# 1__MCU_Breakout.net
KiCad netlist of a schematic drawn in Altium Designer
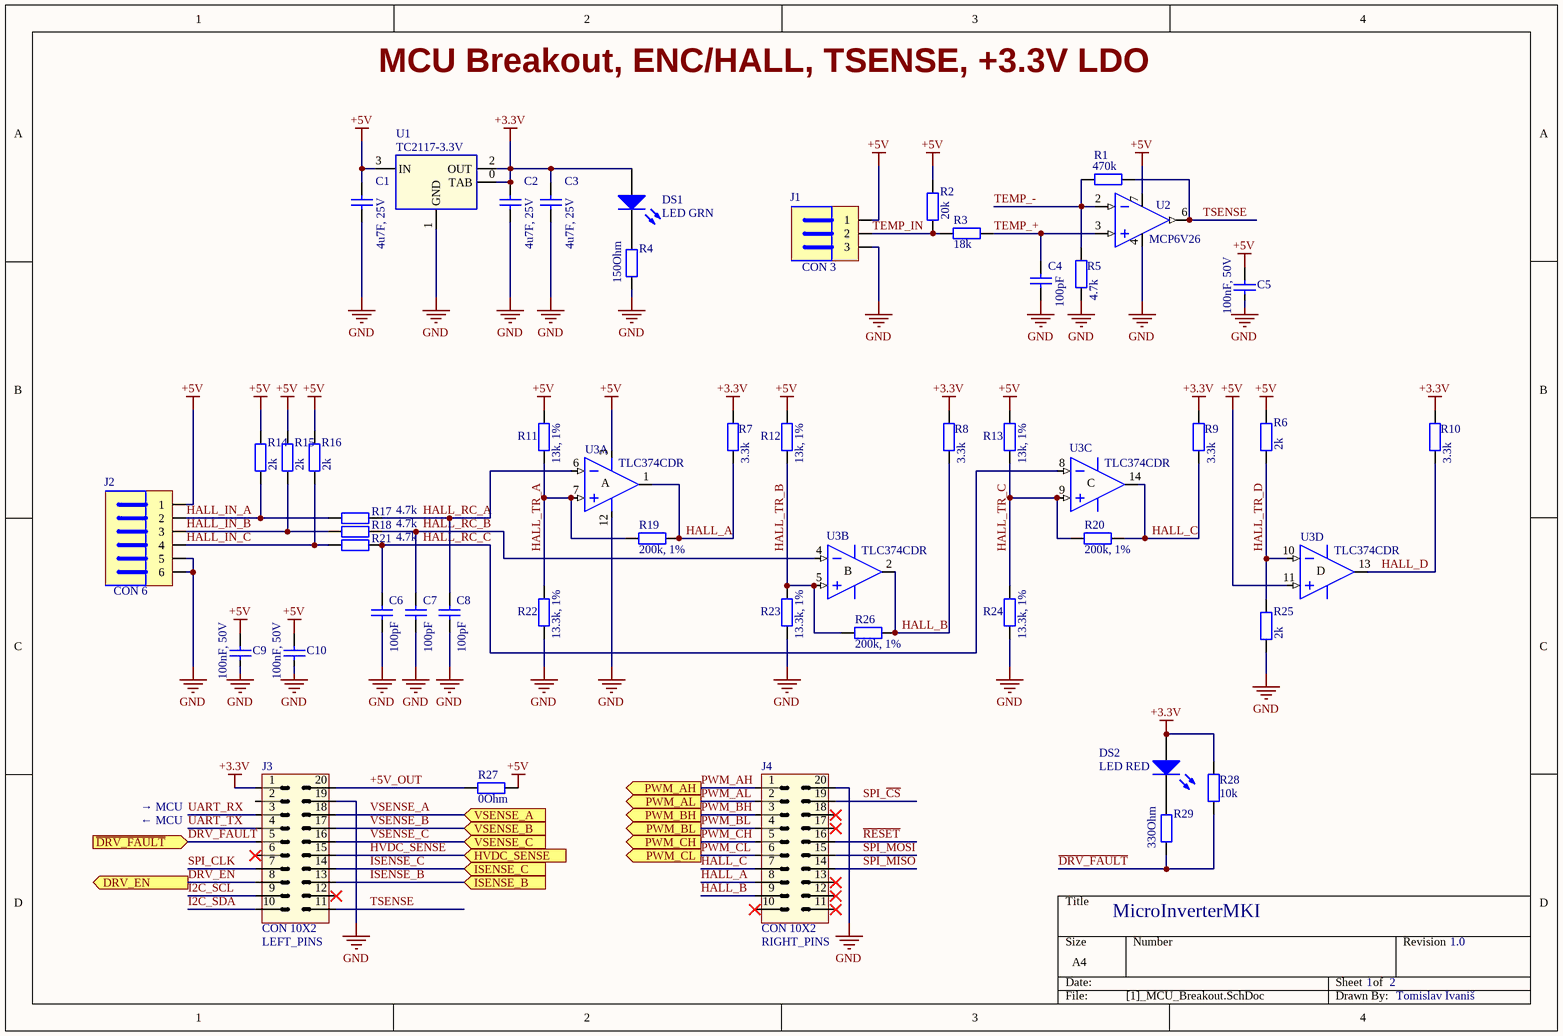
[diagram p0: [1]_MCU_Breakout.SchDoc]

(export (version "E")
  (design (tool "Eeschema 10.0.6"))
  (components
    (comp (ref "C1")
      (value "4u7F, 25V")
      (footprint "0805")
      (description "Capacitor")
      (fields (field (name "MANUFACTURER PART NUMBER") "885012107018"))
      (libsource (lib "MyComponentLib") (part "Cap Semi"))
    )
    (comp (ref "C2")
      (value "4u7F, 25V")
      (footprint "0805")
      (description "Capacitor")
      (fields (field (name "MANUFACTURER PART NUMBER") "885012107018"))
      (libsource (lib "MyComponentLib") (part "Cap Semi"))
    )
    (comp (ref "C3")
      (value "4u7F, 25V")
      (footprint "0805")
      (description "Capacitor")
      (fields (field (name "MANUFACTURER PART NUMBER") "885012107018"))
      (libsource (lib "MyComponentLib") (part "Cap Semi"))
    )
    (comp (ref "C4")
      (value "100pF")
      (footprint "0603")
      (description "885012006036")
      (fields (field (name "MANUFACTURER PART NUMBER") "GCM0335C1E101GA16D"))
      (libsource (lib "MyComponentLib") (part "Cap Semi"))
    )
    (comp (ref "C5")
      (value "100nF, 50V")
      (footprint "0603")
      (description "Capacitor")
      (fields (field (name "MANUFACTURER PART NUMBER") "C0603C104M5RACTU"))
      (libsource (lib "MyComponentLib") (part "Cap Semi"))
    )
    (comp (ref "C6")
      (value "100pF")
      (footprint "0603")
      (description "885012006036")
      (fields (field (name "MANUFACTURER PART NUMBER") "GCM0335C1E101GA16D"))
      (libsource (lib "MyComponentLib") (part "Cap Semi"))
    )
    (comp (ref "C7")
      (value "100pF")
      (footprint "0603")
      (description "885012006036")
      (fields (field (name "MANUFACTURER PART NUMBER") "GCM0335C1E101GA16D"))
      (libsource (lib "MyComponentLib") (part "Cap Semi"))
    )
    (comp (ref "C8")
      (value "100pF")
      (footprint "0603")
      (description "885012006036")
      (fields (field (name "MANUFACTURER PART NUMBER") "GCM0335C1E101GA16D"))
      (libsource (lib "MyComponentLib") (part "Cap Semi"))
    )
    (comp (ref "C9")
      (value "100nF, 50V")
      (footprint "0603")
      (description "Capacitor")
      (fields (field (name "MANUFACTURER PART NUMBER") "C0603C104M5RACTU"))
      (libsource (lib "MyComponentLib") (part "Cap Semi"))
    )
    (comp (ref "C10")
      (value "100nF, 50V")
      (footprint "0603")
      (description "Capacitor")
      (fields (field (name "MANUFACTURER PART NUMBER") "C0603C104M5RACTU"))
      (libsource (lib "MyComponentLib") (part "Cap Semi"))
    )
    (comp (ref "DS1")
      (value "LED GRN")
      (footprint "0805LED")
      (description "Typical RED, GREEN, YELLOW, AMBER GaAs LED")
      (fields (field (name "MANUFACTURER PART NUMBER") "LTST-S220GKT"))
      (libsource (lib "MyComponentLib") (part "LED"))
    )
    (comp (ref "DS2")
      (value "LED RED")
      (footprint "0805LED")
      (description "Typical RED, GREEN, YELLOW, AMBER GaAs LED")
      (fields (field (name "MANUFACTURER PART NUMBER") "LTST-C170KRKT"))
      (libsource (lib "MyComponentLib") (part "LED"))
    )
    (comp (ref "J1")
      (value "CON 3")
      (footprint "CON 3 MOLEX SL")
      (fields (field (name "MANUFACTURER PART NUMBER") "70553-0002"))
      (libsource (lib "MyComponentLib") (part "CON 3 SIL Angle"))
    )
    (comp (ref "J2")
      (value "CON 6")
      (footprint "CON 6 MOLEX SL")
      (fields (field (name "MANUFACTURER PART NUMBER") "70553-0040"))
      (libsource (lib "MyComponentLib") (part "CON 6 SIL Angle"))
    )
    (comp (ref "J3")
      (value "CON 10X2")
      (footprint "CON 20 HEADER - (ALT) - INVERTED")
      (fields (field (name "MANUFACTURER PART NUMBER") "68683-305LF"))
      (libsource (lib "MyComponentLib") (part "CON 10X2"))
    )
    (comp (ref "J4")
      (value "CON 10X2")
      (footprint "CON 20 HEADER - (ALT) - INVERTED")
      (fields (field (name "MANUFACTURER PART NUMBER") "68683-305LF"))
      (libsource (lib "MyComponentLib") (part "CON 10X2"))
    )
    (comp (ref "R1")
      (value "470k")
      (footprint "0805")
      (description "CR0805-JW-680ELF")
      (fields (field (name "MANUFACTURER PART NUMBER") "CR0805-FX-4703ELF"))
      (libsource (lib "") (part "Res_3"))
    )
    (comp (ref "R2")
      (value "20k")
      (footprint "0805")
      (description "CR0805-JW-680ELF")
      (fields (field (name "MANUFACTURER PART NUMBER") "CR0805-FX-2002ELF"))
      (libsource (lib "MyComponentLib") (part "Res"))
    )
    (comp (ref "R3")
      (value "18k")
      (footprint "0805")
      (description "CR0805-JW-680ELF")
      (fields (field (name "MANUFACTURER PART NUMBER") "CR0805-FX-1802ELF"))
      (libsource (lib "") (part "Res_2"))
    )
    (comp (ref "R4")
      (value "150Ohm")
      (footprint "0805")
      (description "CR0805-JW-680ELF")
      (fields (field (name "MANUFACTURER PART NUMBER") "CR0805-JW-151ELF"))
      (libsource (lib "MyComponentLib") (part "Res"))
    )
    (comp (ref "R5")
      (value "4.7k")
      (footprint "0805")
      (description "CR0805-JW-680ELF")
      (fields (field (name "MANUFACTURER PART NUMBER") "CR0805-FX-4701ELF"))
      (libsource (lib "") (part "Res_1"))
    )
    (comp (ref "R6")
      (value "2k")
      (footprint "0805")
      (description "CR0805-JW-680ELF")
      (fields (field (name "MANUFACTURER PART NUMBER") "CR0805-FX-2001ELF"))
      (libsource (lib "MyComponentLib") (part "Res"))
    )
    (comp (ref "R7")
      (value "3.3k")
      (footprint "0805")
      (description "CR0805-JW-680ELF")
      (fields (field (name "MANUFACTURER PART NUMBER") "CR0805-FX-3301ELF"))
      (libsource (lib "MyComponentLib") (part "Res"))
    )
    (comp (ref "R8")
      (value "3.3k")
      (footprint "0805")
      (description "CR0805-JW-680ELF")
      (fields (field (name "MANUFACTURER PART NUMBER") "CR0805-FX-3301ELF"))
      (libsource (lib "MyComponentLib") (part "Res"))
    )
    (comp (ref "R9")
      (value "3.3k")
      (footprint "0805")
      (description "CR0805-JW-680ELF")
      (fields (field (name "MANUFACTURER PART NUMBER") "CR0805-FX-3301ELF"))
      (libsource (lib "MyComponentLib") (part "Res"))
    )
    (comp (ref "R10")
      (value "3.3k")
      (footprint "0805")
      (description "CR0805-JW-680ELF")
      (fields (field (name "MANUFACTURER PART NUMBER") "CR0805-FX-3301ELF"))
      (libsource (lib "MyComponentLib") (part "Res"))
    )
    (comp (ref "R11")
      (value "13k, 1%")
      (footprint "0805")
      (description "CR0805-JW-680ELF")
      (fields (field (name "MANUFACTURER PART NUMBER") "CR0805-FX-1302ELF"))
      (libsource (lib "MyComponentLib") (part "Res"))
    )
    (comp (ref "R12")
      (value "13k, 1%")
      (footprint "0805")
      (description "CR0805-JW-680ELF")
      (fields (field (name "MANUFACTURER PART NUMBER") "CR0805-FX-1302ELF"))
      (libsource (lib "MyComponentLib") (part "Res"))
    )
    (comp (ref "R13")
      (value "13k, 1%")
      (footprint "0805")
      (description "CR0805-JW-680ELF")
      (fields (field (name "MANUFACTURER PART NUMBER") "CR0805-FX-1302ELF"))
      (libsource (lib "MyComponentLib") (part "Res"))
    )
    (comp (ref "R14")
      (value "2k")
      (footprint "0805")
      (description "CR0805-JW-680ELF")
      (fields (field (name "MANUFACTURER PART NUMBER") "CR0805-FX-2001ELF"))
      (libsource (lib "MyComponentLib") (part "Res"))
    )
    (comp (ref "R15")
      (value "2k")
      (footprint "0805")
      (description "CR0805-JW-680ELF")
      (fields (field (name "MANUFACTURER PART NUMBER") "CR0805-FX-2001ELF"))
      (libsource (lib "MyComponentLib") (part "Res"))
    )
    (comp (ref "R16")
      (value "2k")
      (footprint "0805")
      (description "CR0805-JW-680ELF")
      (fields (field (name "MANUFACTURER PART NUMBER") "CR0805-FX-2001ELF"))
      (libsource (lib "MyComponentLib") (part "Res"))
    )
    (comp (ref "R17")
      (value "4.7k")
      (footprint "0805")
      (description "CR0805-JW-680ELF")
      (fields (field (name "MANUFACTURER PART NUMBER") "CR0805-FX-4701ELF"))
      (libsource (lib "") (part "Res_2"))
    )
    (comp (ref "R18")
      (value "4.7k")
      (footprint "0805")
      (description "CR0805-JW-680ELF")
      (fields (field (name "MANUFACTURER PART NUMBER") "CR0805-FX-4701ELF"))
      (libsource (lib "") (part "Res_2"))
    )
    (comp (ref "R19")
      (value "200k, 1%")
      (footprint "0805")
      (description "CR0805-JW-680ELF")
      (fields (field (name "MANUFACTURER PART NUMBER") "CR0805-FX-2003ELF"))
      (libsource (lib "") (part "Res_2"))
    )
    (comp (ref "R20")
      (value "200k, 1%")
      (footprint "0805")
      (description "CR0805-JW-680ELF")
      (fields (field (name "MANUFACTURER PART NUMBER") "CR0805-FX-2003ELF"))
      (libsource (lib "") (part "Res_2"))
    )
    (comp (ref "R21")
      (value "4.7k")
      (footprint "0805")
      (description "CR0805-JW-680ELF")
      (fields (field (name "MANUFACTURER PART NUMBER") "CR0805-FX-4701ELF"))
      (libsource (lib "") (part "Res_2"))
    )
    (comp (ref "R22")
      (value "13.3k, 1%")
      (footprint "0805")
      (description "CR0805-JW-680ELF")
      (fields (field (name "MANUFACTURER PART NUMBER") "CR0805-FX-1332ELF"))
      (libsource (lib "MyComponentLib") (part "Res"))
    )
    (comp (ref "R23")
      (value "13.3k, 1%")
      (footprint "0805")
      (description "CR0805-JW-680ELF")
      (fields (field (name "MANUFACTURER PART NUMBER") "CR0805-FX-1332ELF"))
      (libsource (lib "MyComponentLib") (part "Res"))
    )
    (comp (ref "R24")
      (value "13.3k, 1%")
      (footprint "0805")
      (description "CR0805-JW-680ELF")
      (fields (field (name "MANUFACTURER PART NUMBER") "CR0805-FX-1332ELF"))
      (libsource (lib "MyComponentLib") (part "Res"))
    )
    (comp (ref "R25")
      (value "2k")
      (footprint "0805")
      (description "CR0805-JW-680ELF")
      (fields (field (name "MANUFACTURER PART NUMBER") "CR0805-FX-2001ELF"))
      (libsource (lib "MyComponentLib") (part "Res"))
    )
    (comp (ref "R26")
      (value "200k, 1%")
      (footprint "0805")
      (description "CR0805-JW-680ELF")
      (fields (field (name "MANUFACTURER PART NUMBER") "CR0805-FX-2003ELF"))
      (libsource (lib "") (part "Res_2"))
    )
    (comp (ref "R27")
      (value "0Ohm")
      (footprint "0805")
      (description "Resistor")
      (fields (field (name "MANUFACTURER PART NUMBER") "CR0805-J/-000ELF"))
      (libsource (lib "") (part "Res_2"))
    )
    (comp (ref "R28")
      (value "10k")
      (footprint "0805")
      (description "CR0805-JW-680ELF")
      (fields (field (name "MANUFACTURER PART NUMBER") "CR0805-FX-1002ELF"))
      (libsource (lib "") (part "Res_1"))
    )
    (comp (ref "R29")
      (value "330Ohm")
      (footprint "0805")
      (description "CR0805-JW-680ELF")
      (fields (field (name "MANUFACTURER PART NUMBER") "CR0805-FX-3300ELF"))
      (libsource (lib "MyComponentLib") (part "Res"))
    )
    (comp (ref "U1")
      (value "TC2117-3.3V")
      (footprint "SOT223 (ZLDO)")
      (description "Linear regulator")
      (fields (field (name "MANUFACTURER PART NUMBER") "TC2117-3.3VDBTR"))
      (libsource (lib "MyComponentLib") (part "1117"))
    )
    (comp (ref "U2")
      (value "MCP6V26")
      (footprint "SOIC 8-pin")
      (fields (field (name "MANUFACTURER PART NUMBER") "MCP6V26-E/MS"))
      (libsource (lib "MyComponentLib") (part "OP_AMP_SINGLE_SOIC"))
    )
    (comp (ref "U3")
      (value "TLC374CDR")
      (footprint "SOIC14")
      (description "Comparator, quad, open drain")
      (libsource (lib "MyComponentLib") (part "Comparator Quad"))
    )
  )
  (nets
    (net (code "1") (name "+3.3V") (class "Default")
      (node (ref "C2") (pin "1") (pinfunction "1_1") (pintype "passive"))
      (node (ref "C3") (pin "1") (pinfunction "1_1") (pintype "passive"))
      (node (ref "DS1") (pin "2") (pinfunction "A_2") (pintype "passive"))
      (node (ref "DS2") (pin "2") (pinfunction "A_2") (pintype "passive"))
      (node (ref "J3") (pin "1") (pintype "passive"))
      (node (ref "R10") (pin "1") (pinfunction "1_1") (pintype "passive"))
      (node (ref "R28") (pin "2") (pinfunction "2_2") (pintype "passive"))
      (node (ref "R7") (pin "1") (pinfunction "1_1") (pintype "passive"))
      (node (ref "R8") (pin "1") (pinfunction "1_1") (pintype "passive"))
      (node (ref "R9") (pin "1") (pinfunction "1_1") (pintype "passive"))
      (node (ref "U1") (pin "0") (pinfunction "TAB_0") (pintype "passive"))
      (node (ref "U1") (pin "2") (pinfunction "OUT_2") (pintype "passive"))
    )
    (net (code "2") (name "+5V") (class "Default")
      (node (ref "C1") (pin "1") (pinfunction "1_1") (pintype "passive"))
      (node (ref "C10") (pin "1") (pinfunction "1_1") (pintype "passive"))
      (node (ref "C5") (pin "1") (pinfunction "1_1") (pintype "passive"))
      (node (ref "C9") (pin "1") (pinfunction "1_1") (pintype "passive"))
      (node (ref "J1") (pin "1") (pinfunction "1_1") (pintype "passive"))
      (node (ref "J2") (pin "1") (pinfunction "1_1") (pintype "passive"))
      (node (ref "R11") (pin "1") (pinfunction "1_1") (pintype "passive"))
      (node (ref "R12") (pin "1") (pinfunction "1_1") (pintype "passive"))
      (node (ref "R13") (pin "1") (pinfunction "1_1") (pintype "passive"))
      (node (ref "R14") (pin "1") (pinfunction "1_1") (pintype "passive"))
      (node (ref "R15") (pin "1") (pinfunction "1_1") (pintype "passive"))
      (node (ref "R16") (pin "1") (pinfunction "1_1") (pintype "passive"))
      (node (ref "R2") (pin "1") (pinfunction "1_1") (pintype "passive"))
      (node (ref "R27") (pin "2") (pinfunction "2_2") (pintype "passive"))
      (node (ref "R6") (pin "1") (pinfunction "1_1") (pintype "passive"))
      (node (ref "U1") (pin "3") (pinfunction "IN_3") (pintype "passive"))
      (node (ref "U2") (pin "7") (pinfunction "*_7") (pintype "passive"))
      (node (ref "U3") (pin "11") (pinfunction "IN+_11") (pintype "input"))
      (node (ref "U3") (pin "3") (pinfunction "VDD_3") (pintype "passive"))
    )
    (net (code "3") (name "/+5V_OUT") (class "Default")
      (node (ref "J3") (pin "20") (pintype "passive"))
      (node (ref "R27") (pin "1") (pinfunction "1_1") (pintype "passive"))
    )
    (net (code "4") (name "/DRV_EN") (class "Default") (node (ref "J3") (pin "8") (pintype "passive")))
    (net (code "5") (name "/HALL_A") (class "Default")
      (node (ref "J4") (pin "8") (pintype "passive"))
      (node (ref "R19") (pin "2") (pinfunction "2_2") (pintype "passive"))
      (node (ref "R7") (pin "2") (pinfunction "2_2") (pintype "passive"))
      (node (ref "U3") (pin "1") (pinfunction "OUT_1") (pintype "open_collector"))
    )
    (net (code "6") (name "/HALL_B") (class "Default")
      (node (ref "J4") (pin "9") (pintype "passive"))
      (node (ref "R26") (pin "2") (pinfunction "2_2") (pintype "passive"))
      (node (ref "R8") (pin "2") (pinfunction "2_2") (pintype "passive"))
      (node (ref "U3") (pin "2") (pinfunction "OUT_2") (pintype "open_collector"))
    )
    (net (code "7") (name "/HALL_C") (class "Default")
      (node (ref "J4") (pin "7") (pintype "passive"))
      (node (ref "R20") (pin "2") (pinfunction "2_2") (pintype "passive"))
      (node (ref "R9") (pin "2") (pinfunction "2_2") (pintype "passive"))
      (node (ref "U3") (pin "14") (pinfunction "OUT_14") (pintype "open_collector"))
    )
    (net (code "8") (name "/HALL_D") (class "Default")
      (node (ref "R10") (pin "2") (pinfunction "2_2") (pintype "passive"))
      (node (ref "U3") (pin "13") (pinfunction "OUT_13") (pintype "open_collector"))
    )
    (net (code "9") (name "/HALL_IN_A") (class "Default")
      (node (ref "J2") (pin "2") (pinfunction "2_2") (pintype "passive"))
      (node (ref "R14") (pin "2") (pinfunction "2_2") (pintype "passive"))
      (node (ref "R17") (pin "1") (pinfunction "1_1") (pintype "passive"))
    )
    (net (code "10") (name "/HALL_IN_B") (class "Default")
      (node (ref "J2") (pin "3") (pinfunction "3_3") (pintype "passive"))
      (node (ref "R15") (pin "2") (pinfunction "2_2") (pintype "passive"))
      (node (ref "R18") (pin "1") (pinfunction "1_1") (pintype "passive"))
    )
    (net (code "11") (name "/HALL_IN_C") (class "Default")
      (node (ref "J2") (pin "4") (pinfunction "4_4") (pintype "passive"))
      (node (ref "R16") (pin "2") (pinfunction "2_2") (pintype "passive"))
      (node (ref "R21") (pin "1") (pinfunction "1_1") (pintype "passive"))
    )
    (net (code "12") (name "/HALL_RC_A") (class "Default")
      (node (ref "C8") (pin "1") (pinfunction "1_1") (pintype "passive"))
      (node (ref "R17") (pin "2") (pinfunction "2_2") (pintype "passive"))
      (node (ref "U3") (pin "6") (pinfunction "IN-_6") (pintype "input"))
    )
    (net (code "13") (name "/HALL_RC_B") (class "Default")
      (node (ref "C7") (pin "1") (pinfunction "1_1") (pintype "passive"))
      (node (ref "R18") (pin "2") (pinfunction "2_2") (pintype "passive"))
      (node (ref "U3") (pin "4") (pinfunction "IN-_4") (pintype "input"))
    )
    (net (code "14") (name "/HALL_RC_C") (class "Default")
      (node (ref "C6") (pin "1") (pinfunction "1_1") (pintype "passive"))
      (node (ref "R21") (pin "2") (pinfunction "2_2") (pintype "passive"))
      (node (ref "U3") (pin "8") (pinfunction "IN-_8") (pintype "input"))
    )
    (net (code "15") (name "/HALL_TR_A") (class "Default")
      (node (ref "R11") (pin "2") (pinfunction "2_2") (pintype "passive"))
      (node (ref "R19") (pin "1") (pinfunction "1_1") (pintype "passive"))
      (node (ref "R22") (pin "1") (pinfunction "1_1") (pintype "passive"))
      (node (ref "U3") (pin "7") (pinfunction "IN+_7") (pintype "input"))
    )
    (net (code "16") (name "/HALL_TR_B") (class "Default")
      (node (ref "R12") (pin "2") (pinfunction "2_2") (pintype "passive"))
      (node (ref "R23") (pin "1") (pinfunction "1_1") (pintype "passive"))
      (node (ref "R26") (pin "1") (pinfunction "1_1") (pintype "passive"))
      (node (ref "U3") (pin "5") (pinfunction "IN+_5") (pintype "input"))
    )
    (net (code "17") (name "/HALL_TR_C") (class "Default")
      (node (ref "R13") (pin "2") (pinfunction "2_2") (pintype "passive"))
      (node (ref "R20") (pin "1") (pinfunction "1_1") (pintype "passive"))
      (node (ref "R24") (pin "1") (pinfunction "1_1") (pintype "passive"))
      (node (ref "U3") (pin "9") (pinfunction "IN+_9") (pintype "input"))
    )
    (net (code "18") (name "/HALL_TR_D") (class "Default")
      (node (ref "R25") (pin "1") (pinfunction "1_1") (pintype "passive"))
      (node (ref "R6") (pin "2") (pinfunction "2_2") (pintype "passive"))
      (node (ref "U3") (pin "10") (pinfunction "IN-_10") (pintype "input"))
    )
    (net (code "19") (name "/HVDC_SENSE") (class "Default") (node (ref "J3") (pin "15") (pintype "passive")))
    (net (code "20") (name "/I2C_SCL") (class "Default") (node (ref "J3") (pin "9") (pintype "passive")))
    (net (code "21") (name "/I2C_SDA") (class "Default") (node (ref "J3") (pin "10") (pintype "passive")))
    (net (code "22") (name "/ISENSE_B") (class "Default") (node (ref "J3") (pin "13") (pintype "passive")))
    (net (code "23") (name "/ISENSE_C") (class "Default") (node (ref "J3") (pin "14") (pintype "passive")))
    (net (code "24") (name "/PWM_AH") (class "Default") (node (ref "J4") (pin "1") (pintype "passive")))
    (net (code "25") (name "/PWM_AL") (class "Default") (node (ref "J4") (pin "2") (pintype "passive")))
    (net (code "26") (name "/PWM_BH") (class "Default") (node (ref "J4") (pin "3") (pintype "passive")))
    (net (code "27") (name "/PWM_BL") (class "Default") (node (ref "J4") (pin "4") (pintype "passive")))
    (net (code "28") (name "/PWM_CH") (class "Default") (node (ref "J4") (pin "5") (pintype "passive")))
    (net (code "29") (name "/PWM_CL") (class "Default") (node (ref "J4") (pin "6") (pintype "passive")))
    (net (code "30") (name "/SPI_CLK") (class "Default") (node (ref "J3") (pin "7") (pintype "passive")))
    (net (code "31") (name "/SPI_MISO") (class "Default") (node (ref "J4") (pin "14") (pintype "passive")))
    (net (code "32") (name "/SPI_MOSI") (class "Default") (node (ref "J4") (pin "15") (pintype "passive")))
    (net (code "33") (name "/SPI_~{CS}") (class "Default") (node (ref "J4") (pin "19") (pintype "passive")))
    (net (code "34") (name "/TEMP_+") (class "Default")
      (node (ref "C4") (pin "1") (pinfunction "1_1") (pintype "passive"))
      (node (ref "R3") (pin "2") (pinfunction "2_2") (pintype "passive"))
      (node (ref "U2") (pin "3") (pinfunction "IN+_3") (pintype "input"))
    )
    (net (code "35") (name "/TEMP_-") (class "Default")
      (node (ref "R1") (pin "2") (pinfunction "2_2") (pintype "passive"))
      (node (ref "R5") (pin "2") (pinfunction "2_2") (pintype "passive"))
      (node (ref "U2") (pin "2") (pinfunction "IN-_2") (pintype "input"))
    )
    (net (code "36") (name "/TEMP_IN") (class "Default")
      (node (ref "J1") (pin "2") (pinfunction "2_2") (pintype "passive"))
      (node (ref "R2") (pin "2") (pinfunction "2_2") (pintype "passive"))
      (node (ref "R3") (pin "1") (pinfunction "1_1") (pintype "passive"))
    )
    (net (code "37") (name "/TSENSE") (class "Default")
      (node (ref "J3") (pin "11") (pintype "passive"))
      (node (ref "R1") (pin "1") (pinfunction "1_1") (pintype "passive"))
      (node (ref "U2") (pin "6") (pinfunction "OUT_6") (pintype "output"))
    )
    (net (code "38") (name "/UART_RX") (class "Default") (node (ref "J3") (pin "3") (pintype "passive")))
    (net (code "39") (name "/UART_TX") (class "Default") (node (ref "J3") (pin "4") (pintype "passive")))
    (net (code "40") (name "/VSENSE_A") (class "Default") (node (ref "J3") (pin "18") (pintype "passive")))
    (net (code "41") (name "/VSENSE_B") (class "Default") (node (ref "J3") (pin "17") (pintype "passive")))
    (net (code "42") (name "/VSENSE_C") (class "Default") (node (ref "J3") (pin "16") (pintype "passive")))
    (net (code "43") (name "/~{DRV_FAULT}") (class "Default")
      (node (ref "J3") (pin "5") (pintype "passive"))
      (node (ref "R28") (pin "1") (pinfunction "1_1") (pintype "passive"))
      (node (ref "R29") (pin "2") (pinfunction "2_2") (pintype "passive"))
    )
    (net (code "44") (name "/~{RESET}") (class "Default") (node (ref "J4") (pin "16") (pintype "passive")))
    (net (code "45") (name "GND") (class "Default")
      (node (ref "C1") (pin "2") (pinfunction "2_2") (pintype "passive"))
      (node (ref "C10") (pin "2") (pinfunction "2_2") (pintype "passive"))
      (node (ref "C2") (pin "2") (pinfunction "2_2") (pintype "passive"))
      (node (ref "C3") (pin "2") (pinfunction "2_2") (pintype "passive"))
      (node (ref "C4") (pin "2") (pinfunction "2_2") (pintype "passive"))
      (node (ref "C5") (pin "2") (pinfunction "2_2") (pintype "passive"))
      (node (ref "C6") (pin "2") (pinfunction "2_2") (pintype "passive"))
      (node (ref "C7") (pin "2") (pinfunction "2_2") (pintype "passive"))
      (node (ref "C8") (pin "2") (pinfunction "2_2") (pintype "passive"))
      (node (ref "C9") (pin "2") (pinfunction "2_2") (pintype "passive"))
      (node (ref "J1") (pin "3") (pinfunction "3_3") (pintype "passive"))
      (node (ref "J2") (pin "5") (pinfunction "5_5") (pintype "passive"))
      (node (ref "J2") (pin "6") (pinfunction "6_6") (pintype "passive"))
      (node (ref "J3") (pin "19") (pintype "passive"))
      (node (ref "J4") (pin "20") (pintype "passive"))
      (node (ref "R22") (pin "2") (pinfunction "2_2") (pintype "passive"))
      (node (ref "R23") (pin "2") (pinfunction "2_2") (pintype "passive"))
      (node (ref "R24") (pin "2") (pinfunction "2_2") (pintype "passive"))
      (node (ref "R25") (pin "2") (pinfunction "2_2") (pintype "passive"))
      (node (ref "R4") (pin "2") (pinfunction "2_2") (pintype "passive"))
      (node (ref "R5") (pin "1") (pinfunction "1_1") (pintype "passive"))
      (node (ref "U1") (pin "1") (pinfunction "GND_1") (pintype "passive"))
      (node (ref "U2") (pin "4") (pinfunction "*_4") (pintype "passive"))
      (node (ref "U3") (pin "12") (pinfunction "GND_12") (pintype "passive"))
    )
    (net (code "46") (name "Net-(DS1-K)") (class "Default")
      (node (ref "DS1") (pin "1") (pinfunction "K_1") (pintype "passive"))
      (node (ref "R4") (pin "1") (pinfunction "1_1") (pintype "passive"))
    )
    (net (code "47") (name "Net-(DS2-K)") (class "Default")
      (node (ref "DS2") (pin "1") (pinfunction "K_1") (pintype "passive"))
      (node (ref "R29") (pin "1") (pinfunction "1_1") (pintype "passive"))
    )
    (net (code "48") (name "unconnected-(J3-Pad2)") (class "Default")
      (node (ref "J3") (pin "2") (pintype "passive"))
    )
    (net (code "49") (name "unconnected-(J3-Pad6)") (class "Default")
      (node (ref "J3") (pin "6") (pintype "passive+no_connect"))
    )
    (net (code "50") (name "unconnected-(J3-Pad12)") (class "Default")
      (node (ref "J3") (pin "12") (pintype "passive+no_connect"))
    )
    (net (code "51") (name "unconnected-(J4-Pad10)") (class "Default")
      (node (ref "J4") (pin "10") (pintype "passive+no_connect"))
    )
    (net (code "52") (name "unconnected-(J4-Pad11)") (class "Default")
      (node (ref "J4") (pin "11") (pintype "passive+no_connect"))
    )
    (net (code "53") (name "unconnected-(J4-Pad12)") (class "Default")
      (node (ref "J4") (pin "12") (pintype "passive+no_connect"))
    )
    (net (code "54") (name "unconnected-(J4-Pad13)") (class "Default")
      (node (ref "J4") (pin "13") (pintype "passive+no_connect"))
    )
    (net (code "55") (name "unconnected-(J4-Pad17)") (class "Default")
      (node (ref "J4") (pin "17") (pintype "passive+no_connect"))
    )
    (net (code "56") (name "unconnected-(J4-Pad18)") (class "Default")
      (node (ref "J4") (pin "18") (pintype "passive+no_connect"))
    )
  )
)
